# SUP_2_5_FMC.net
KiCad netlist of a schematic drawn in Altium Designer
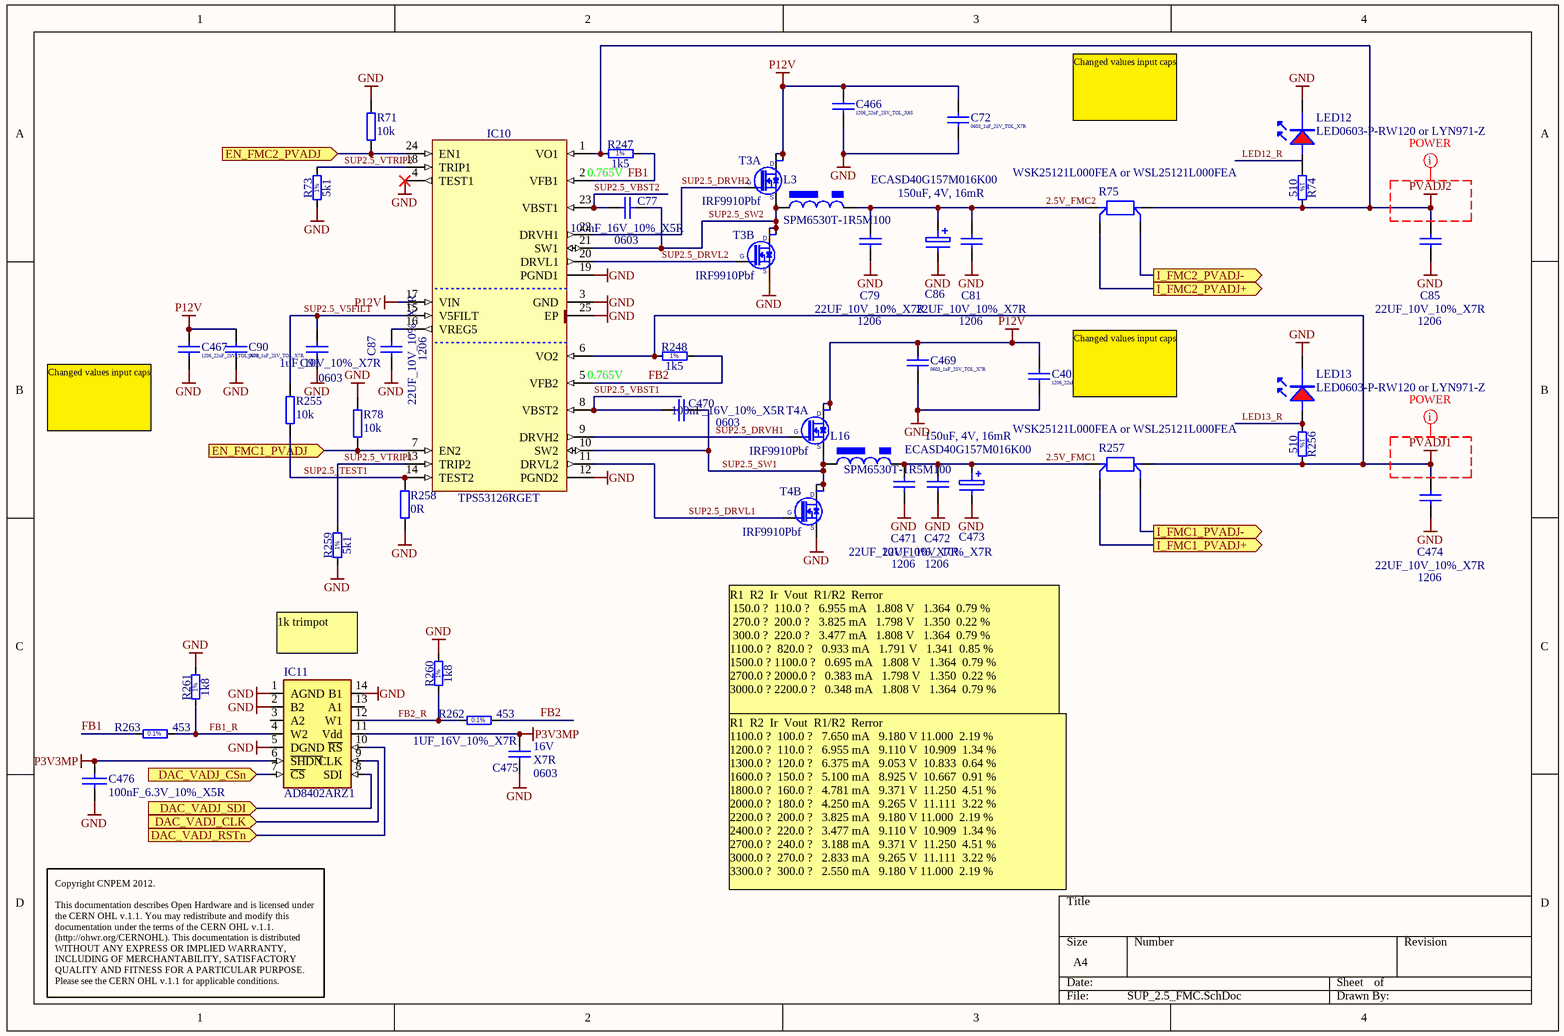
[diagram p0: SUP_2.5_FMC.SchDoc]

(export (version "E")
  (design (tool "Eeschema 10.0.6"))
  (components
    (comp (ref "C40")
      (value "1206_22uF_25V_TOL_X6S")
      (footprint "CAPC3225X140N")
      (fields (field (name "PART NUMBER") "Ceramic_1206"))
      (libsource (lib "Capacitors") (part "Capacitor"))
    )
    (comp (ref "C72")
      (value "0603_1uF_25V_TOL_X7R")
      (footprint "CAPC1608X90N")
      (fields (field (name "PART NUMBER") "Ceramic_0603"))
      (libsource (lib "Capacitors") (part "Capacitor"))
    )
    (comp (ref "C77")
      (value "100nF_16V_10%_X5R")
      (footprint "0402C")
      (description "Non-polarised capacitor")
      (fields
        (field (name "PART NUMBER") "CC0603_100NF_50V_10%_X7R")
        (field (name "VOLTAGE") "50V")
        (field (name "CASE") "0603")
        (field (name "AUTHOR") "CERN DEM JLC")
      )
      (libsource (lib "Capacitors") (part "Capacitor - non polarized"))
    )
    (comp (ref "C79")
      (value "22UF_10V_10%_X7R")
      (footprint "1206C")
      (description "Non-polarised capacitor")
      (fields
        (field (name "PART NUMBER") "CC1206_22UF_10V_10%_X7R")
        (field (name "VOLTAGE") "10V")
        (field (name "CASE") "1206")
        (field (name "AUTHOR") "CERN DEM JLC")
      )
      (libsource (lib "Capacitors") (part "Capacitor - non polarized"))
    )
    (comp (ref "C81")
      (value "22UF_10V_10%_X7R")
      (footprint "1206C")
      (description "Non-polarised capacitor")
      (fields
        (field (name "PART NUMBER") "CC1206_22UF_10V_10%_X7R")
        (field (name "VOLTAGE") "10V")
        (field (name "CASE") "1206")
        (field (name "AUTHOR") "CERN DEM JLC")
      )
      (libsource (lib "Capacitors") (part "Capacitor - non polarized"))
    )
    (comp (ref "C85")
      (value "22UF_10V_10%_X7R")
      (footprint "1206C")
      (description "Non-polarised capacitor")
      (fields
        (field (name "PART NUMBER") "CC1206_22UF_10V_10%_X7R")
        (field (name "VOLTAGE") "10V")
        (field (name "CASE") "1206")
        (field (name "AUTHOR") "CERN DEM JLC")
      )
      (libsource (lib "Capacitors") (part "Capacitor - non polarized"))
    )
    (comp (ref "C86")
      (value "ECASD40G157M016K00")
      (footprint "2917_POLY")
      (description "POLY, 150uF, 4V, ESR: 16mR")
      (fields (field (name "ALTIUM_VALUE") "150uF, 4V, 16mR"))
      (libsource (lib "LIBRARY_SCH") (part "CAP_POLYMER_SMDD"))
    )
    (comp (ref "C87")
      (value "22UF_10V_10%_X7R")
      (footprint "1206C")
      (description "Non-polarised capacitor")
      (fields
        (field (name "PART NUMBER") "CC1206_22UF_10V_10%_X7R")
        (field (name "VOLTAGE") "10V")
        (field (name "CASE") "1206")
        (field (name "AUTHOR") "CERN DEM JLC")
      )
      (libsource (lib "Capacitors") (part "Capacitor - non polarized"))
    )
    (comp (ref "C90")
      (value "0603_1uF_25V_TOL_X7R")
      (footprint "CAPC1608X90N")
      (fields (field (name "PART NUMBER") "Ceramic_0603"))
      (libsource (lib "Capacitors") (part "Capacitor"))
    )
    (comp (ref "C91")
      (value "1uF_10V_10%_X7R")
      (footprint "0603C")
      (description "Non-polarised capacitor")
      (fields
        (field (name "PART NUMBER") "CC0603_1UF_16V_10%_X7R")
        (field (name "VOLTAGE") "16V")
        (field (name "CASE") "0603")
        (field (name "AUTHOR") "CERN DEM JLC")
      )
      (libsource (lib "Capacitors") (part "Capacitor - non polarized"))
    )
    (comp (ref "C466")
      (value "1206_22uF_25V_TOL_X6S")
      (footprint "CAPC3225X140N")
      (fields (field (name "PART NUMBER") "Ceramic_1206"))
      (libsource (lib "Capacitors") (part "Capacitor"))
    )
    (comp (ref "C467")
      (value "1206_22uF_25V_TOL_X7R")
      (footprint "CAPC3225X140N")
      (fields (field (name "PART NUMBER") "Ceramic_1206"))
      (libsource (lib "Capacitors") (part "Capacitor"))
    )
    (comp (ref "C469")
      (value "0603_1uF_25V_TOL_X7R")
      (footprint "CAPC1608X90N")
      (fields (field (name "PART NUMBER") "Ceramic_0603"))
      (libsource (lib "Capacitors") (part "Capacitor"))
    )
    (comp (ref "C470")
      (value "100nF_16V_10%_X5R")
      (footprint "0402C")
      (description "Non-polarised capacitor")
      (fields
        (field (name "PART NUMBER") "CC0603_100NF_50V_10%_X7R")
        (field (name "VOLTAGE") "50V")
        (field (name "CASE") "0603")
        (field (name "AUTHOR") "CERN DEM JLC")
      )
      (libsource (lib "Capacitors") (part "Capacitor - non polarized"))
    )
    (comp (ref "C471")
      (value "22UF_10V_10%_X7R")
      (footprint "1206C")
      (description "Non-polarised capacitor")
      (fields
        (field (name "PART NUMBER") "CC1206_22UF_10V_10%_X7R")
        (field (name "VOLTAGE") "10V")
        (field (name "CASE") "1206")
        (field (name "AUTHOR") "CERN DEM JLC")
      )
      (libsource (lib "Capacitors") (part "Capacitor - non polarized"))
    )
    (comp (ref "C472")
      (value "22UF_10V_10%_X7R")
      (footprint "1206C")
      (description "Non-polarised capacitor")
      (fields
        (field (name "PART NUMBER") "CC1206_22UF_10V_10%_X7R")
        (field (name "VOLTAGE") "10V")
        (field (name "CASE") "1206")
        (field (name "AUTHOR") "CERN DEM JLC")
      )
      (libsource (lib "Capacitors") (part "Capacitor - non polarized"))
    )
    (comp (ref "C473")
      (value "ECASD40G157M016K00")
      (footprint "2917_POLY")
      (description "POLY, 150uF, 4V, ESR: 16mR")
      (fields (field (name "ALTIUM_VALUE") "150uF, 4V, 16mR"))
      (libsource (lib "LIBRARY_SCH") (part "CAP_POLYMER_SMDD"))
    )
    (comp (ref "C474")
      (value "22UF_10V_10%_X7R")
      (footprint "1206C")
      (description "Non-polarised capacitor")
      (fields
        (field (name "PART NUMBER") "CC1206_22UF_10V_10%_X7R")
        (field (name "VOLTAGE") "10V")
        (field (name "CASE") "1206")
        (field (name "AUTHOR") "CERN DEM JLC")
      )
      (libsource (lib "Capacitors") (part "Capacitor - non polarized"))
    )
    (comp (ref "C475")
      (value "1UF_16V_10%_X7R")
      (footprint "0603C")
      (description "Non-polarised capacitor")
      (fields
        (field (name "PART NUMBER") "CC0603_1UF_16V_10%_X7R")
        (field (name "VOLTAGE") "16V")
        (field (name "TC") "X7R")
        (field (name "TOLERANCE") "±10%")
        (field (name "CASE") "0603")
        (field (name "AUTHOR") "CERN DEM JLC")
      )
      (libsource (lib "Capacitors") (part "Capacitor - non polarized"))
    )
    (comp (ref "C476")
      (value "100nF_6.3V_10%_X5R")
      (footprint "0201C")
      (description "Capacitor SMD")
      (libsource (lib "LIBRARY_SCH") (part "CAP_SMD_0201"))
    )
    (comp (ref "IC10")
      (value "TPS53126RGET")
      (footprint "QFN50P400X400X100-25N-S255")
      (description "Dual Synchronous Step-Down Controller For Low Voltage Power Rails")
      (fields (field (name "MANUFACTURER") "TEXAS INSTRUMENTS") (field (name "AUTHOR") "CERN DEM JLC"))
      (libsource (lib "ICs And Semiconductors") (part "TPS53126RGET"))
    )
    (comp (ref "IC11")
      (value "AD8402ARZ1")
      (footprint "SO-14")
      (description "1k dual digital potentiometer")
      (libsource (lib "LIBRARY_SCH") (part "DAC_AD8402"))
    )
    (comp (ref "L3")
      (value "SPM6530T-1R5M100")
      (footprint "IND_TDK_SPM6530")
      (description "1.5uH, 20%, 10mR, 11.5A")
      (libsource (lib "LIBRARY_SCH") (part "L_POWER_SPM6530T"))
    )
    (comp (ref "L16")
      (value "SPM6530T-1R5M100")
      (footprint "IND_TDK_SPM6530")
      (description "1.5uH, 20%, 10mR, 11.5A")
      (libsource (lib "LIBRARY_SCH") (part "L_POWER_SPM6530T"))
    )
    (comp (ref "LED12")
      (value "LED0603-P-RW120 or LYN971-Z")
      (footprint "led_0603R")
      (description "LED 0603 red")
      (libsource (lib "LIBRARY_SCH") (part "LED_0603R"))
    )
    (comp (ref "LED13")
      (value "LED0603-P-RW120 or LYN971-Z")
      (footprint "led_0603R")
      (description "LED 0603 red")
      (libsource (lib "LIBRARY_SCH") (part "LED_0603R"))
    )
    (comp (ref "R71")
      (value "10k")
      (footprint "0402R")
      (description "SMD Resistor")
      (libsource (lib "LIBRARY_SCH") (part "RES_0402"))
    )
    (comp (ref "R73")
      (value "5k1")
      (footprint "0603R")
      (description "Resistor - 1%")
      (fields
        (field (name "PART NUMBER") "R0603_5K1_1%_0.1W_100PPM")
        (field (name "POWER") "0.1W")
        (field (name "AUTHOR") "CERN DEM JLC")
      )
      (libsource (lib "Resistors") (part "Resistor - 1%"))
    )
    (comp (ref "R74")
      (value "510")
      (footprint "0603R")
      (description "Resistor - 1%")
      (fields
        (field (name "PART NUMBER") "R0402_510R_1%_0.0625W_100PPM")
        (field (name "POWER") "0.0625W")
        (field (name "AUTHOR") "CERN DEM JLC")
      )
      (libsource (lib "Resistors") (part "Resistor - 1%"))
    )
    (comp (ref "R75")
      (value "WSK25121L000FEA or WSL25121L000FEA")
      (footprint "RES_WSK2512")
      (description "RESISTOR, METAL STRIP, 0.001 OHM 1%")
      (libsource (lib "LIBRARY_SCH") (part "RES_POW_Kelvin"))
    )
    (comp (ref "R78")
      (value "10k")
      (footprint "0402R")
      (description "SMD Resistor")
      (libsource (lib "LIBRARY_SCH") (part "RES_0402"))
    )
    (comp (ref "R247")
      (value "1k5")
      (footprint "RESC1608X55N")
      (description "Resistor - 1%")
      (fields
        (field (name "PART NUMBER") "R0603_1K5_1%_0.1W_100PPM")
        (field (name "POWER") "0.1W")
        (field (name "AUTHOR") "CERN DEM JLC")
      )
      (libsource (lib "Resistors") (part "Resistor - 1%"))
    )
    (comp (ref "R248")
      (value "1k5")
      (footprint "RESC1608X55N")
      (description "Resistor - 1%")
      (fields
        (field (name "PART NUMBER") "R0603_1K5_1%_0.1W_100PPM")
        (field (name "POWER") "0.1W")
        (field (name "AUTHOR") "CERN DEM JLC")
      )
      (libsource (lib "Resistors") (part "Resistor - 1%"))
    )
    (comp (ref "R255")
      (value "10k")
      (footprint "0402R")
      (description "SMD Resistor")
      (libsource (lib "LIBRARY_SCH") (part "RES_0402"))
    )
    (comp (ref "R256")
      (value "510")
      (footprint "0603R")
      (description "Resistor - 1%")
      (fields
        (field (name "PART NUMBER") "R0402_510R_1%_0.0625W_100PPM")
        (field (name "POWER") "0.0625W")
        (field (name "AUTHOR") "CERN DEM JLC")
      )
      (libsource (lib "Resistors") (part "Resistor - 1%"))
    )
    (comp (ref "R257")
      (value "WSK25121L000FEA or WSL25121L000FEA")
      (footprint "RES_WSK2512")
      (description "RESISTOR, METAL STRIP, 0.001 OHM 1%")
      (libsource (lib "LIBRARY_SCH") (part "RES_POW_Kelvin"))
    )
    (comp (ref "R258")
      (value "0R")
      (footprint "0402R")
      (description "SMD Resistor")
      (libsource (lib "LIBRARY_SCH") (part "RES_0402"))
    )
    (comp (ref "R259")
      (value "5k1")
      (footprint "0603R")
      (description "Resistor - 1%")
      (fields
        (field (name "PART NUMBER") "R0603_5K1_1%_0.1W_100PPM")
        (field (name "POWER") "0.1W")
        (field (name "AUTHOR") "CERN DEM JLC")
      )
      (libsource (lib "Resistors") (part "Resistor - 1%"))
    )
    (comp (ref "R260")
      (value "1k8")
      (footprint "RESC1608X55N")
      (description "Resistor - 1%")
      (fields
        (field (name "PART NUMBER") "R0603_910R_1%_0.1W_100PPM")
        (field (name "POWER") "0.1W")
        (field (name "AUTHOR") "CERN DEM JLC")
      )
      (libsource (lib "Resistors") (part "Resistor - 1%"))
    )
    (comp (ref "R261")
      (value "1k8")
      (footprint "RESC1608X55N")
      (description "Resistor - 1%")
      (fields
        (field (name "PART NUMBER") "R0603_910R_1%_0.1W_100PPM")
        (field (name "POWER") "0.1W")
        (field (name "AUTHOR") "CERN DEM JLC")
      )
      (libsource (lib "Resistors") (part "Resistor - 1%"))
    )
    (comp (ref "R262")
      (value "453")
      (footprint "RESC1608X55N")
      (description "Resistor - 0.1%")
      (fields
        (field (name "PART NUMBER") "R0603_453R_0.1%_0.063W_10PPM")
        (field (name "POWER") "0.063W")
        (field (name "AUTHOR") "CERN DEM JLC")
      )
      (libsource (lib "Resistors") (part "Resistor - 0.1%"))
    )
    (comp (ref "R263")
      (value "453")
      (footprint "RESC1608X55N")
      (description "Resistor - 0.1%")
      (fields
        (field (name "PART NUMBER") "R0603_453R_0.1%_0.063W_10PPM")
        (field (name "POWER") "0.063W")
        (field (name "AUTHOR") "CERN DEM JLC")
      )
      (libsource (lib "Resistors") (part "Resistor - 0.1%"))
    )
    (comp (ref "T3")
      (value "IRF9910Pbf")
      (footprint "SOIC127P600X175-8N")
      (description "Dual SO-8 MOSFET For POL Cconverter")
      (fields (field (name "MANUFACTURER") "INTERNATIONAL RECTIFIER") (field (name "AUTHOR") "CERN DEM JLC"))
      (libsource (lib "ICs And Semiconductors") (part "IRF9910"))
    )
    (comp (ref "T4")
      (value "IRF9910Pbf")
      (footprint "SOIC127P600X175-8N")
      (description "Dual SO-8 MOSFET For POL Cconverter")
      (fields (field (name "MANUFACTURER") "INTERNATIONAL RECTIFIER") (field (name "AUTHOR") "CERN DEM JLC"))
      (libsource (lib "ICs And Semiconductors") (part "IRF9910"))
    )
  )
  (nets
    (net (code "1") (name "/2.5V_FMC1") (class "Default")
      (node (ref "C471") (pin "1") (pinfunction "1_1") (pintype "passive"))
      (node (ref "C472") (pin "1") (pinfunction "1_1") (pintype "passive"))
      (node (ref "C473") (pin "1") (pinfunction "1_1") (pintype "passive"))
      (node (ref "L16") (pin "2") (pintype "passive"))
      (node (ref "R257") (pin "1") (pinfunction "1_1") (pintype "passive"))
    )
    (net (code "2") (name "/2.5V_FMC2") (class "Default")
      (node (ref "C79") (pin "1") (pinfunction "1_1") (pintype "passive"))
      (node (ref "C81") (pin "1") (pinfunction "1_1") (pintype "passive"))
      (node (ref "C86") (pin "1") (pinfunction "1_1") (pintype "passive"))
      (node (ref "L3") (pin "2") (pintype "passive"))
      (node (ref "R75") (pin "1") (pinfunction "1_1") (pintype "passive"))
    )
    (net (code "3") (name "/DAC_VADJ_CLK") (class "Default")
      (node (ref "IC11") (pin "9") (pinfunction "CLK_9") (pintype "input"))
    )
    (net (code "4") (name "/DAC_VADJ_CSn") (class "Default")
      (node (ref "IC11") (pin "7") (pinfunction "~{CS}_7") (pintype "input"))
    )
    (net (code "5") (name "/DAC_VADJ_RSTn") (class "Default")
      (node (ref "IC11") (pin "10") (pinfunction "~{RS}_10") (pintype "input"))
    )
    (net (code "6") (name "/DAC_VADJ_SDI") (class "Default")
      (node (ref "IC11") (pin "8") (pinfunction "SDI_8") (pintype "input"))
    )
    (net (code "7") (name "/EN_FMC1_PVADJ") (class "Default")
      (node (ref "IC10") (pin "7") (pinfunction "EN2_7") (pintype "input"))
      (node (ref "R78") (pin "1") (pinfunction "1_1") (pintype "passive"))
    )
    (net (code "8") (name "/EN_FMC2_PVADJ") (class "Default")
      (node (ref "IC10") (pin "24") (pinfunction "EN1_24") (pintype "input"))
      (node (ref "R71") (pin "1") (pinfunction "1_1") (pintype "passive"))
    )
    (net (code "9") (name "/FB1") (class "Default")
      (node (ref "IC10") (pin "2") (pinfunction "VFB1_2") (pintype "input"))
      (node (ref "R247") (pin "2") (pinfunction "2_2") (pintype "passive"))
      (node (ref "R263") (pin "1") (pinfunction "1_1") (pintype "passive"))
    )
    (net (code "10") (name "/FB1_R") (class "Default")
      (node (ref "IC11") (pin "4") (pinfunction "W2_4") (pintype "passive"))
      (node (ref "R261") (pin "1") (pinfunction "1_1") (pintype "passive"))
      (node (ref "R263") (pin "2") (pinfunction "2_2") (pintype "passive"))
    )
    (net (code "11") (name "/FB2") (class "Default")
      (node (ref "IC10") (pin "5") (pinfunction "VFB2_5") (pintype "input"))
      (node (ref "R248") (pin "2") (pinfunction "2_2") (pintype "passive"))
      (node (ref "R262") (pin "2") (pinfunction "2_2") (pintype "passive"))
    )
    (net (code "12") (name "/FB2_R") (class "Default")
      (node (ref "IC11") (pin "12") (pinfunction "W1_12") (pintype "passive"))
      (node (ref "R260") (pin "1") (pinfunction "1_1") (pintype "passive"))
      (node (ref "R262") (pin "1") (pinfunction "1_1") (pintype "passive"))
    )
    (net (code "13") (name "/I_FMC1_PVADJ+") (class "Default")
      (node (ref "R257") (pin "1a") (pinfunction "1a_1a") (pintype "passive"))
    )
    (net (code "14") (name "/I_FMC1_PVADJ-") (class "Default")
      (node (ref "R257") (pin "2a") (pinfunction "2a_2a") (pintype "passive"))
    )
    (net (code "15") (name "/I_FMC2_PVADJ+") (class "Default")
      (node (ref "R75") (pin "1a") (pinfunction "1a_1a") (pintype "passive"))
    )
    (net (code "16") (name "/I_FMC2_PVADJ-") (class "Default")
      (node (ref "R75") (pin "2a") (pinfunction "2a_2a") (pintype "passive"))
    )
    (net (code "18") (name "/LED13_R") (class "Default")
      (node (ref "LED13") (pin "A") (pinfunction "A_A") (pintype "passive"))
      (node (ref "R256") (pin "1") (pinfunction "1_1") (pintype "passive"))
    )
    (net (code "19") (name "/SUP2.5_DRVH1") (class "Default")
      (node (ref "IC10") (pin "9") (pinfunction "DRVH2_9") (pintype "output"))
      (node (ref "T4") (pin "4") (pinfunction "G_4") (pintype "passive"))
    )
    (net (code "20") (name "/SUP2.5_DRVH2") (class "Default")
      (node (ref "IC10") (pin "22") (pinfunction "DRVH1_22") (pintype "output"))
      (node (ref "T3") (pin "4") (pinfunction "G_4") (pintype "passive"))
    )
    (net (code "21") (name "/SUP2.5_DRVL1") (class "Default")
      (node (ref "IC10") (pin "11") (pinfunction "DRVL2_11") (pintype "output"))
      (node (ref "T4") (pin "2") (pinfunction "G_2") (pintype "passive"))
    )
    (net (code "22") (name "/SUP2.5_DRVL2") (class "Default")
      (node (ref "IC10") (pin "20") (pinfunction "DRVL1_20") (pintype "output"))
      (node (ref "T3") (pin "2") (pinfunction "G_2") (pintype "passive"))
    )
    (net (code "23") (name "/SUP2.5_SW1") (class "Default")
      (node (ref "C470") (pin "1") (pinfunction "1_1") (pintype "passive"))
      (node (ref "IC10") (pin "10") (pinfunction "SW2_10") (pintype "bidirectional"))
      (node (ref "L16") (pin "1") (pintype "passive"))
      (node (ref "T4") (pin "3") (pinfunction "S_3") (pintype "passive"))
      (node (ref "T4") (pin "7") (pinfunction "D_7") (pintype "passive"))
      (node (ref "T4") (pin "8") (pinfunction "D_8") (pintype "passive"))
    )
    (net (code "24") (name "/SUP2.5_SW2") (class "Default")
      (node (ref "C77") (pin "1") (pinfunction "1_1") (pintype "passive"))
      (node (ref "IC10") (pin "21") (pinfunction "SW1_21") (pintype "bidirectional"))
      (node (ref "L3") (pin "1") (pintype "passive"))
      (node (ref "T3") (pin "3") (pinfunction "S_3") (pintype "passive"))
      (node (ref "T3") (pin "7") (pinfunction "D_7") (pintype "passive"))
      (node (ref "T3") (pin "8") (pinfunction "D_8") (pintype "passive"))
    )
    (net (code "25") (name "/SUP2.5_TEST1") (class "Default")
      (node (ref "IC10") (pin "14") (pinfunction "TEST2_14") (pintype "input"))
      (node (ref "R255") (pin "1") (pinfunction "1_1") (pintype "passive"))
      (node (ref "R258") (pin "2") (pinfunction "2_2") (pintype "passive"))
    )
    (net (code "26") (name "/SUP2.5_V5FILT") (class "Default")
      (node (ref "C91") (pin "2") (pinfunction "2_2") (pintype "passive"))
      (node (ref "IC10") (pin "15") (pinfunction "V5FILT_15") (pintype "input"))
      (node (ref "R255") (pin "2") (pinfunction "2_2") (pintype "passive"))
    )
    (net (code "27") (name "/SUP2.5_VBST1") (class "Default")
      (node (ref "C470") (pin "2") (pinfunction "2_2") (pintype "passive"))
      (node (ref "IC10") (pin "8") (pinfunction "VBST2_8") (pintype "input"))
    )
    (net (code "28") (name "/SUP2.5_VBST2") (class "Default")
      (node (ref "C77") (pin "2") (pinfunction "2_2") (pintype "passive"))
      (node (ref "IC10") (pin "23") (pinfunction "VBST1_23") (pintype "input"))
    )
    (net (code "29") (name "/SUP2.5_VTRIP1") (class "Default")
      (node (ref "IC10") (pin "13") (pinfunction "TRIP2_13") (pintype "input"))
      (node (ref "R259") (pin "2") (pinfunction "2_2") (pintype "passive"))
    )
    (net (code "30") (name "/SUP2.5_VTRIP2") (class "Default")
      (node (ref "IC10") (pin "18") (pinfunction "TRIP1_18") (pintype "input"))
      (node (ref "R73") (pin "2") (pinfunction "2_2") (pintype "passive"))
    )
    (net (code "31") (name "GND") (class "Default")
      (node (ref "C40") (pin "1") (pinfunction "1_1") (pintype "passive"))
      (node (ref "C466") (pin "1") (pinfunction "1_1") (pintype "passive"))
      (node (ref "C467") (pin "1") (pinfunction "1_1") (pintype "passive"))
      (node (ref "C469") (pin "1") (pinfunction "1_1") (pintype "passive"))
      (node (ref "C471") (pin "2") (pinfunction "2_2") (pintype "passive"))
      (node (ref "C472") (pin "2") (pinfunction "2_2") (pintype "passive"))
      (node (ref "C473") (pin "2") (pinfunction "2_2") (pintype "passive"))
      (node (ref "C474") (pin "2") (pinfunction "2_2") (pintype "passive"))
      (node (ref "C475") (pin "1") (pinfunction "1_1") (pintype "passive"))
      (node (ref "C476") (pin "2") (pinfunction "2_2") (pintype "passive"))
      (node (ref "C72") (pin "1") (pinfunction "1_1") (pintype "passive"))
      (node (ref "C79") (pin "2") (pinfunction "2_2") (pintype "passive"))
      (node (ref "C81") (pin "2") (pinfunction "2_2") (pintype "passive"))
      (node (ref "C85") (pin "2") (pinfunction "2_2") (pintype "passive"))
      (node (ref "C86") (pin "2") (pinfunction "2_2") (pintype "passive"))
      (node (ref "C87") (pin "1") (pinfunction "1_1") (pintype "passive"))
      (node (ref "C90") (pin "1") (pinfunction "1_1") (pintype "passive"))
      (node (ref "C91") (pin "1") (pinfunction "1_1") (pintype "passive"))
      (node (ref "IC10") (pin "12") (pinfunction "PGND2_12") (pintype "power_in"))
      (node (ref "IC10") (pin "19") (pinfunction "PGND1_19") (pintype "power_in"))
      (node (ref "IC10") (pin "25") (pinfunction "EP_25") (pintype "power_in"))
      (node (ref "IC10") (pin "3") (pinfunction "GND_3") (pintype "power_in"))
      (node (ref "IC10") (pin "4") (pinfunction "TEST1_4") (pintype "output"))
      (node (ref "IC11") (pin "1") (pinfunction "AGND_1") (pintype "power_in"))
      (node (ref "IC11") (pin "14") (pinfunction "B1_14") (pintype "passive"))
      (node (ref "IC11") (pin "2") (pinfunction "B2_2") (pintype "passive"))
      (node (ref "IC11") (pin "5") (pinfunction "DGND_5") (pintype "power_in"))
      (node (ref "LED12") (pin "K") (pinfunction "K_K") (pintype "passive"))
      (node (ref "LED13") (pin "K") (pinfunction "K_K") (pintype "passive"))
      (node (ref "R258") (pin "1") (pinfunction "1_1") (pintype "passive"))
      (node (ref "R259") (pin "1") (pinfunction "1_1") (pintype "passive"))
      (node (ref "R260") (pin "2") (pinfunction "2_2") (pintype "passive"))
      (node (ref "R261") (pin "2") (pinfunction "2_2") (pintype "passive"))
      (node (ref "R71") (pin "2") (pinfunction "2_2") (pintype "passive"))
      (node (ref "R73") (pin "1") (pinfunction "1_1") (pintype "passive"))
      (node (ref "R78") (pin "2") (pinfunction "2_2") (pintype "passive"))
      (node (ref "T3") (pin "1") (pinfunction "S_1") (pintype "passive"))
      (node (ref "T4") (pin "1") (pinfunction "S_1") (pintype "passive"))
    )
    (net (code "32") (name "Net-(IC10-VREG5)") (class "Default")
      (node (ref "C87") (pin "2") (pinfunction "2_2") (pintype "passive"))
      (node (ref "IC10") (pin "16") (pinfunction "VREG5_16") (pintype "output"))
    )
    (net (code "33") (name "Net-(LED12-PadA)") (class "Default")
      (node (ref "LED12") (pin "A") (pinfunction "A_A") (pintype "passive"))
      (node (ref "R74") (pin "1") (pinfunction "1_1") (pintype "passive"))
    )
    (net (code "34") (name "P3V3MP") (class "Default")
      (node (ref "C475") (pin "2") (pinfunction "2_2") (pintype "passive"))
      (node (ref "C476") (pin "1") (pinfunction "1_1") (pintype "passive"))
      (node (ref "IC11") (pin "11") (pinfunction "Vdd_11") (pintype "power_in"))
      (node (ref "IC11") (pin "6") (pinfunction "~{SHDN}_6") (pintype "input"))
    )
    (net (code "35") (name "P12V") (class "Default")
      (node (ref "C40") (pin "2") (pinfunction "2_2") (pintype "passive"))
      (node (ref "C466") (pin "2") (pinfunction "2_2") (pintype "passive"))
      (node (ref "C467") (pin "2") (pinfunction "2_2") (pintype "passive"))
      (node (ref "C469") (pin "2") (pinfunction "2_2") (pintype "passive"))
      (node (ref "C72") (pin "2") (pinfunction "2_2") (pintype "passive"))
      (node (ref "C90") (pin "2") (pinfunction "2_2") (pintype "passive"))
      (node (ref "IC10") (pin "17") (pinfunction "VIN_17") (pintype "input"))
      (node (ref "T3") (pin "5") (pinfunction "D_5") (pintype "passive"))
      (node (ref "T3") (pin "6") (pinfunction "D_6") (pintype "passive"))
      (node (ref "T4") (pin "5") (pinfunction "D_5") (pintype "passive"))
      (node (ref "T4") (pin "6") (pinfunction "D_6") (pintype "passive"))
    )
    (net (code "36") (name "PVADJ1") (class "Default")
      (node (ref "C474") (pin "1") (pinfunction "1_1") (pintype "passive"))
      (node (ref "IC10") (pin "6") (pinfunction "VO2_6") (pintype "input"))
      (node (ref "R248") (pin "1") (pinfunction "1_1") (pintype "passive"))
      (node (ref "R256") (pin "2") (pinfunction "2_2") (pintype "passive"))
      (node (ref "R257") (pin "2") (pinfunction "2_2") (pintype "passive"))
    )
    (net (code "37") (name "PVADJ2") (class "Default")
      (node (ref "C85") (pin "1") (pinfunction "1_1") (pintype "passive"))
      (node (ref "IC10") (pin "1") (pinfunction "VO1_1") (pintype "input"))
      (node (ref "R247") (pin "1") (pinfunction "1_1") (pintype "passive"))
      (node (ref "R74") (pin "2") (pinfunction "2_2") (pintype "passive"))
      (node (ref "R75") (pin "2") (pinfunction "2_2") (pintype "passive"))
    )
    (net (code "38") (name "unconnected-(IC11-A1-Pad13)") (class "Default")
      (node (ref "IC11") (pin "13") (pinfunction "A1_13") (pintype "passive"))
    )
    (net (code "39") (name "unconnected-(IC11-A2-Pad3)") (class "Default")
      (node (ref "IC11") (pin "3") (pinfunction "A2_3") (pintype "passive"))
    )
  )
)
